# Clover.net
KiCad netlist of a schematic drawn in EAGLE
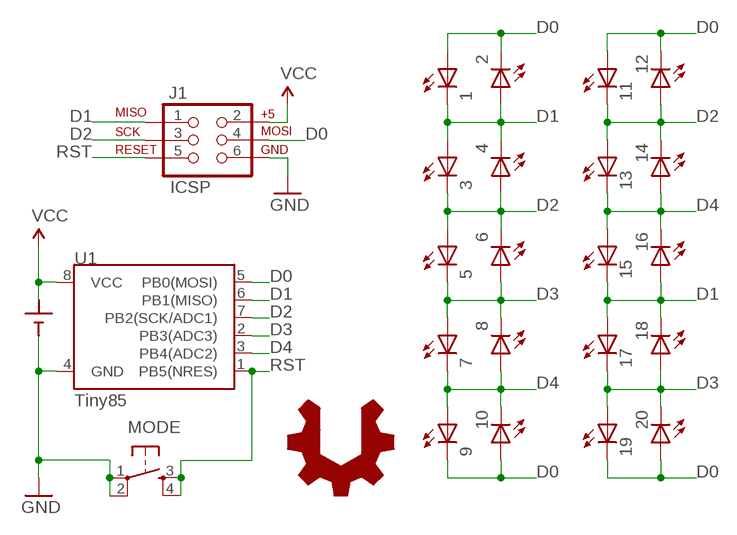
[diagram p0: schematic, sheet 1]

(export (version "E")
  (design (tool "Eeschema 10.0.6"))
  (components
    (comp (ref "1")
      (value "LED5MM")
      (footprint "eagle-import:LED5MM")
      (libsource (lib "eagle-import") (part "LED5MM"))
    )
    (comp (ref "2")
      (value "LED5MM")
      (footprint "eagle-import:LED5MM")
      (libsource (lib "eagle-import") (part "LED5MM"))
    )
    (comp (ref "3")
      (value "LED5MM")
      (footprint "eagle-import:LED5MM")
      (libsource (lib "eagle-import") (part "LED5MM"))
    )
    (comp (ref "4")
      (value "LED5MM")
      (footprint "eagle-import:LED5MM")
      (libsource (lib "eagle-import") (part "LED5MM"))
    )
    (comp (ref "5")
      (value "LED5MM")
      (footprint "eagle-import:LED5MM")
      (libsource (lib "eagle-import") (part "LED5MM"))
    )
    (comp (ref "6")
      (value "LED5MM")
      (footprint "eagle-import:LED5MM")
      (libsource (lib "eagle-import") (part "LED5MM"))
    )
    (comp (ref "7")
      (value "LED5MM")
      (footprint "eagle-import:LED5MM")
      (libsource (lib "eagle-import") (part "LED5MM"))
    )
    (comp (ref "8")
      (value "LED5MM")
      (footprint "eagle-import:LED5MM")
      (libsource (lib "eagle-import") (part "LED5MM"))
    )
    (comp (ref "9")
      (value "LED5MM")
      (footprint "eagle-import:LED5MM")
      (libsource (lib "eagle-import") (part "LED5MM"))
    )
    (comp (ref "10")
      (value "LED5MM")
      (footprint "eagle-import:LED5MM")
      (libsource (lib "eagle-import") (part "LED5MM"))
    )
    (comp (ref "11")
      (value "LED5MM")
      (footprint "eagle-import:LED5MM")
      (libsource (lib "eagle-import") (part "LED5MM"))
    )
    (comp (ref "12")
      (value "LED5MM")
      (footprint "eagle-import:LED5MM")
      (libsource (lib "eagle-import") (part "LED5MM"))
    )
    (comp (ref "13")
      (value "LED5MM")
      (footprint "eagle-import:LED5MM")
      (libsource (lib "eagle-import") (part "LED5MM"))
    )
    (comp (ref "14")
      (value "LED5MM")
      (footprint "eagle-import:LED5MM")
      (libsource (lib "eagle-import") (part "LED5MM"))
    )
    (comp (ref "15")
      (value "LED5MM")
      (footprint "eagle-import:LED5MM")
      (libsource (lib "eagle-import") (part "LED5MM"))
    )
    (comp (ref "16")
      (value "LED5MM")
      (footprint "eagle-import:LED5MM")
      (libsource (lib "eagle-import") (part "LED5MM"))
    )
    (comp (ref "17")
      (value "LED5MM")
      (footprint "eagle-import:LED5MM")
      (libsource (lib "eagle-import") (part "LED5MM"))
    )
    (comp (ref "18")
      (value "LED5MM")
      (footprint "eagle-import:LED5MM")
      (libsource (lib "eagle-import") (part "LED5MM"))
    )
    (comp (ref "19")
      (value "LED5MM")
      (footprint "eagle-import:LED5MM")
      (libsource (lib "eagle-import") (part "LED5MM"))
    )
    (comp (ref "20")
      (value "LED5MM")
      (footprint "eagle-import:LED5MM")
      (libsource (lib "eagle-import") (part "LED5MM"))
    )
    (comp (ref "BATT")
      (value "CR2032")
      (footprint "eagle-import:CR2032-THRU")
      (libsource (lib "eagle-import") (part "BATTCR2032_THRU"))
    )
    (comp (ref "J1")
      (value "ICSP")
      (footprint "eagle-import:2X3-NS")
      (libsource (lib "eagle-import") (part "AVR_SPI_PRG_6LABELED"))
    )
    (comp (ref "MODE")
      (value "TAC_SWITCHPTH")
      (footprint "eagle-import:TACTILE-PTH")
      (libsource (lib "eagle-import") (part "TAC_SWITCHPTH"))
    )
    (comp (ref "U$1")
      (value "USER_HACKABLE")
      (footprint "eagle-import:USER_HACKABLE")
      (libsource (lib "eagle-import") (part "USER_HACKABLE"))
    )
    (comp (ref "U1")
      (value "Tiny85")
      (footprint "eagle-import:DIP08")
      (libsource (lib "eagle-import") (part "ATTINY45TINY85-20-DIP"))
    )
  )
  (nets
    (net (code "1") (name "/D0") (class "Default")
      (node (ref "1") (pin "A") (pinfunction "A_A") (pintype "passive"))
      (node (ref "10") (pin "A") (pinfunction "A_A") (pintype "passive"))
      (node (ref "11") (pin "A") (pinfunction "A_A") (pintype "passive"))
      (node (ref "12") (pin "K") (pinfunction "C_K") (pintype "passive"))
      (node (ref "19") (pin "K") (pinfunction "C_K") (pintype "passive"))
      (node (ref "2") (pin "K") (pinfunction "C_K") (pintype "passive"))
      (node (ref "20") (pin "A") (pinfunction "A_A") (pintype "passive"))
      (node (ref "9") (pin "K") (pinfunction "C_K") (pintype "passive"))
      (node (ref "J1") (pin "4") (pinfunction "MOSI_4") (pintype "passive"))
      (node (ref "U1") (pin "5") (pinfunction "PB0(MOSI)_5") (pintype "bidirectional"))
    )
    (net (code "2") (name "/D1") (class "Default")
      (node (ref "1") (pin "K") (pinfunction "C_K") (pintype "passive"))
      (node (ref "15") (pin "K") (pinfunction "C_K") (pintype "passive"))
      (node (ref "16") (pin "A") (pinfunction "A_A") (pintype "passive"))
      (node (ref "17") (pin "A") (pinfunction "A_A") (pintype "passive"))
      (node (ref "18") (pin "K") (pinfunction "C_K") (pintype "passive"))
      (node (ref "2") (pin "A") (pinfunction "A_A") (pintype "passive"))
      (node (ref "3") (pin "A") (pinfunction "A_A") (pintype "passive"))
      (node (ref "4") (pin "K") (pinfunction "C_K") (pintype "passive"))
      (node (ref "J1") (pin "1") (pinfunction "MISO_1") (pintype "passive"))
      (node (ref "U1") (pin "6") (pinfunction "PB1(MISO)_6") (pintype "bidirectional"))
    )
    (net (code "3") (name "/D2") (class "Default")
      (node (ref "11") (pin "K") (pinfunction "C_K") (pintype "passive"))
      (node (ref "12") (pin "A") (pinfunction "A_A") (pintype "passive"))
      (node (ref "13") (pin "A") (pinfunction "A_A") (pintype "passive"))
      (node (ref "14") (pin "K") (pinfunction "C_K") (pintype "passive"))
      (node (ref "3") (pin "K") (pinfunction "C_K") (pintype "passive"))
      (node (ref "4") (pin "A") (pinfunction "A_A") (pintype "passive"))
      (node (ref "5") (pin "A") (pinfunction "A_A") (pintype "passive"))
      (node (ref "6") (pin "K") (pinfunction "C_K") (pintype "passive"))
      (node (ref "J1") (pin "3") (pinfunction "SCK_3") (pintype "passive"))
      (node (ref "U1") (pin "7") (pinfunction "PB2(SCK/ADC1)_7") (pintype "bidirectional"))
    )
    (net (code "4") (name "/D3") (class "Default")
      (node (ref "17") (pin "K") (pinfunction "C_K") (pintype "passive"))
      (node (ref "18") (pin "A") (pinfunction "A_A") (pintype "passive"))
      (node (ref "19") (pin "A") (pinfunction "A_A") (pintype "passive"))
      (node (ref "20") (pin "K") (pinfunction "C_K") (pintype "passive"))
      (node (ref "5") (pin "K") (pinfunction "C_K") (pintype "passive"))
      (node (ref "6") (pin "A") (pinfunction "A_A") (pintype "passive"))
      (node (ref "7") (pin "A") (pinfunction "A_A") (pintype "passive"))
      (node (ref "8") (pin "K") (pinfunction "C_K") (pintype "passive"))
      (node (ref "U1") (pin "2") (pinfunction "PB3(ADC3)_2") (pintype "bidirectional"))
    )
    (net (code "5") (name "/D4") (class "Default")
      (node (ref "10") (pin "K") (pinfunction "C_K") (pintype "passive"))
      (node (ref "13") (pin "K") (pinfunction "C_K") (pintype "passive"))
      (node (ref "14") (pin "A") (pinfunction "A_A") (pintype "passive"))
      (node (ref "15") (pin "A") (pinfunction "A_A") (pintype "passive"))
      (node (ref "16") (pin "K") (pinfunction "C_K") (pintype "passive"))
      (node (ref "7") (pin "K") (pinfunction "C_K") (pintype "passive"))
      (node (ref "8") (pin "A") (pinfunction "A_A") (pintype "passive"))
      (node (ref "9") (pin "A") (pinfunction "A_A") (pintype "passive"))
      (node (ref "U1") (pin "3") (pinfunction "PB4(ADC2)_3") (pintype "bidirectional"))
    )
    (net (code "6") (name "/RST") (class "Default")
      (node (ref "J1") (pin "5") (pinfunction "RST_5") (pintype "passive"))
      (node (ref "MODE") (pin "3") (pinfunction "3_3") (pintype "passive"))
      (node (ref "MODE") (pin "4") (pinfunction "4_4") (pintype "passive"))
      (node (ref "U1") (pin "1") (pinfunction "PB5(NRES)_1") (pintype "bidirectional"))
    )
    (net (code "7") (name "GND") (class "Default")
      (node (ref "BATT") (pin "-") (pinfunction "-_-") (pintype "power_in"))
      (node (ref "J1") (pin "6") (pinfunction "GND_6") (pintype "passive"))
      (node (ref "MODE") (pin "1") (pinfunction "1_1") (pintype "passive"))
      (node (ref "MODE") (pin "2") (pinfunction "2_2") (pintype "passive"))
      (node (ref "U1") (pin "4") (pinfunction "GND_4") (pintype "bidirectional"))
    )
    (net (code "8") (name "VCC") (class "Default")
      (node (ref "BATT") (pin "+1") (pinfunction "+_+1") (pintype "power_in"))
      (node (ref "J1") (pin "2") (pinfunction "V+_2") (pintype "passive"))
      (node (ref "U1") (pin "8") (pinfunction "VCC_8") (pintype "bidirectional"))
    )
  )
)
